# 06_FPGA_SOC_Part2.net
KiCad netlist of a schematic drawn in Altium Designer
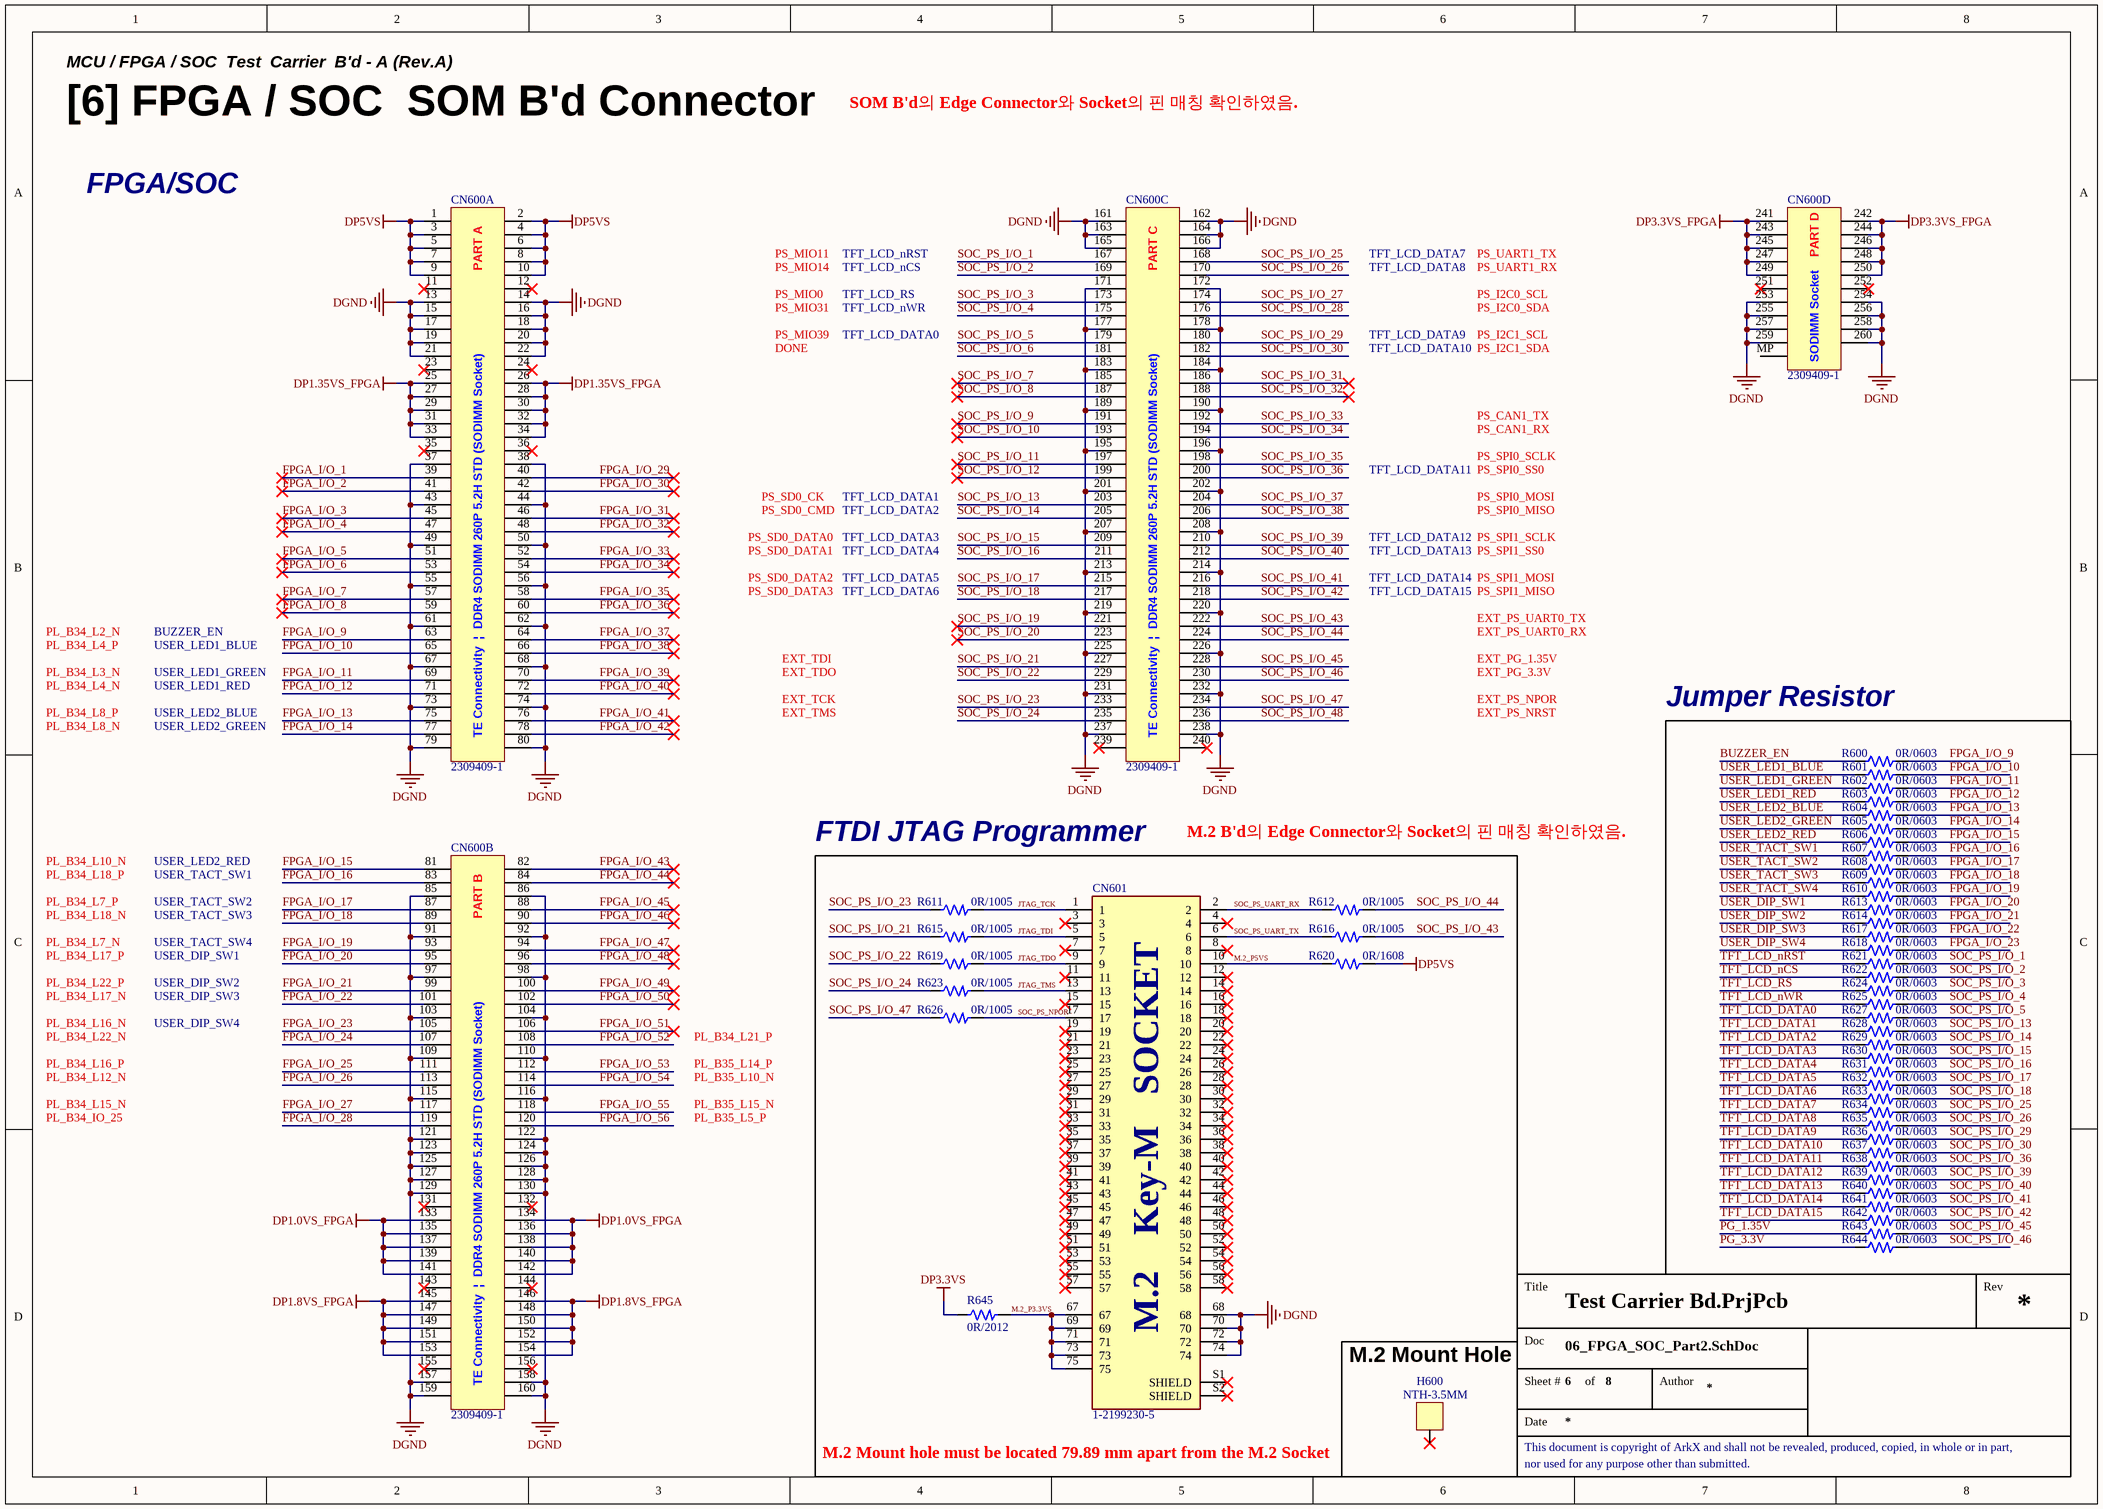
[diagram p0: 06_FPGA_SOC_Part2.SchDoc]

(export (version "E")
  (design (tool "Eeschema 10.0.6"))
  (components
    (comp (ref "CN600")
      (value "2309409-1")
      (footprint "CON_SODIMM_2309409-1")
      (fields (field (name "MANUFACTURER") "TE Connectivity") (field (name "LCSC PART #") "C5164025"))
      (libsource (lib "Arkx") (part "CON_SODIMM_2309409-1"))
    )
    (comp (ref "CN601")
      (value "1-2199230-5")
      (footprint "CON_M.2-KEY-M_FEMALE_1-2199230-5")
      (description "M.2 NGFF Key M Card Edge Connector 0.5mm Pitch 67 Position 4.2mm Height")
      (fields (field (name "MANUFACTURER") "TE Connectivity") (field (name "LCSC PART #") "C590854"))
      (libsource (lib "Arkx") (part "CON_M.2-KEY-M_FEMALE_1-2199230-5"))
    )
    (comp (ref "H600")
      (value "NTH-3.5MM")
      (footprint "HOLE_NTH-3.5MM")
      (description "Non-Through Hole 3.5mm")
      (libsource (lib "Arkx") (part "HOLE_NTH-3.5MM"))
    )
    (comp (ref "R600")
      (value "0R/0603")
      (footprint "RES 0603 (0201_inch)")
      (description "50mW Thick Film Resistors 25V ±1% 0Ω 0201  Chip Resistor - Surface Mount ROHS")
      (fields (field (name "LCSC PART #") "C106227"))
      (libsource (lib "Arkx") (part "RES_0R/0603/50mW"))
    )
    (comp (ref "R601")
      (value "0R/0603")
      (footprint "RES 0603 (0201_inch)")
      (description "50mW Thick Film Resistors 25V ±1% 0Ω 0201  Chip Resistor - Surface Mount ROHS")
      (fields (field (name "LCSC PART #") "C106227"))
      (libsource (lib "Arkx") (part "RES_0R/0603/50mW"))
    )
    (comp (ref "R602")
      (value "0R/0603")
      (footprint "RES 0603 (0201_inch)")
      (description "50mW Thick Film Resistors 25V ±1% 0Ω 0201  Chip Resistor - Surface Mount ROHS")
      (fields (field (name "LCSC PART #") "C106227"))
      (libsource (lib "Arkx") (part "RES_0R/0603/50mW"))
    )
    (comp (ref "R603")
      (value "0R/0603")
      (footprint "RES 0603 (0201_inch)")
      (description "50mW Thick Film Resistors 25V ±1% 0Ω 0201  Chip Resistor - Surface Mount ROHS")
      (fields (field (name "LCSC PART #") "C106227"))
      (libsource (lib "Arkx") (part "RES_0R/0603/50mW"))
    )
    (comp (ref "R604")
      (value "0R/0603")
      (footprint "RES 0603 (0201_inch)")
      (description "50mW Thick Film Resistors 25V ±1% 0Ω 0201  Chip Resistor - Surface Mount ROHS")
      (fields (field (name "LCSC PART #") "C106227"))
      (libsource (lib "Arkx") (part "RES_0R/0603/50mW"))
    )
    (comp (ref "R605")
      (value "0R/0603")
      (footprint "RES 0603 (0201_inch)")
      (description "50mW Thick Film Resistors 25V ±1% 0Ω 0201  Chip Resistor - Surface Mount ROHS")
      (fields (field (name "LCSC PART #") "C106227"))
      (libsource (lib "Arkx") (part "RES_0R/0603/50mW"))
    )
    (comp (ref "R606")
      (value "0R/0603")
      (footprint "RES 0603 (0201_inch)")
      (description "50mW Thick Film Resistors 25V ±1% 0Ω 0201  Chip Resistor - Surface Mount ROHS")
      (fields (field (name "LCSC PART #") "C106227"))
      (libsource (lib "Arkx") (part "RES_0R/0603/50mW"))
    )
    (comp (ref "R607")
      (value "0R/0603")
      (footprint "RES 0603 (0201_inch)")
      (description "50mW Thick Film Resistors 25V ±1% 0Ω 0201  Chip Resistor - Surface Mount ROHS")
      (fields (field (name "LCSC PART #") "C106227"))
      (libsource (lib "Arkx") (part "RES_0R/0603/50mW"))
    )
    (comp (ref "R608")
      (value "0R/0603")
      (footprint "RES 0603 (0201_inch)")
      (description "50mW Thick Film Resistors 25V ±1% 0Ω 0201  Chip Resistor - Surface Mount ROHS")
      (fields (field (name "LCSC PART #") "C106227"))
      (libsource (lib "Arkx") (part "RES_0R/0603/50mW"))
    )
    (comp (ref "R609")
      (value "0R/0603")
      (footprint "RES 0603 (0201_inch)")
      (description "50mW Thick Film Resistors 25V ±1% 0Ω 0201  Chip Resistor - Surface Mount ROHS")
      (fields (field (name "LCSC PART #") "C106227"))
      (libsource (lib "Arkx") (part "RES_0R/0603/50mW"))
    )
    (comp (ref "R610")
      (value "0R/0603")
      (footprint "RES 0603 (0201_inch)")
      (description "50mW Thick Film Resistors 25V ±1% 0Ω 0201  Chip Resistor - Surface Mount ROHS")
      (fields (field (name "LCSC PART #") "C106227"))
      (libsource (lib "Arkx") (part "RES_0R/0603/50mW"))
    )
    (comp (ref "R611")
      (value "0R/1005")
      (footprint "RES 1005 (0402_inch)")
      (description "RES_0R/1005/62.5mW")
      (fields (field (name "LCSC PART #") "C17168"))
      (libsource (lib "Arkx") (part "RES_0R/1005/62.5mW"))
    )
    (comp (ref "R612")
      (value "0R/1005")
      (footprint "RES 1005 (0402_inch)")
      (description "RES_0R/1005/62.5mW")
      (fields (field (name "LCSC PART #") "C17168"))
      (libsource (lib "Arkx") (part "RES_0R/1005/62.5mW"))
    )
    (comp (ref "R613")
      (value "0R/0603")
      (footprint "RES 0603 (0201_inch)")
      (description "50mW Thick Film Resistors 25V ±1% 0Ω 0201  Chip Resistor - Surface Mount ROHS")
      (fields (field (name "LCSC PART #") "C106227"))
      (libsource (lib "Arkx") (part "RES_0R/0603/50mW"))
    )
    (comp (ref "R614")
      (value "0R/0603")
      (footprint "RES 0603 (0201_inch)")
      (description "50mW Thick Film Resistors 25V ±1% 0Ω 0201  Chip Resistor - Surface Mount ROHS")
      (fields (field (name "LCSC PART #") "C106227"))
      (libsource (lib "Arkx") (part "RES_0R/0603/50mW"))
    )
    (comp (ref "R615")
      (value "0R/1005")
      (footprint "RES 1005 (0402_inch)")
      (description "RES_0R/1005/62.5mW")
      (fields (field (name "LCSC PART #") "C17168"))
      (libsource (lib "Arkx") (part "RES_0R/1005/62.5mW"))
    )
    (comp (ref "R616")
      (value "0R/1005")
      (footprint "RES 1005 (0402_inch)")
      (description "RES_0R/1005/62.5mW")
      (fields (field (name "LCSC PART #") "C17168"))
      (libsource (lib "Arkx") (part "RES_0R/1005/62.5mW"))
    )
    (comp (ref "R617")
      (value "0R/0603")
      (footprint "RES 0603 (0201_inch)")
      (description "50mW Thick Film Resistors 25V ±1% 0Ω 0201  Chip Resistor - Surface Mount ROHS")
      (fields (field (name "LCSC PART #") "C106227"))
      (libsource (lib "Arkx") (part "RES_0R/0603/50mW"))
    )
    (comp (ref "R618")
      (value "0R/0603")
      (footprint "RES 0603 (0201_inch)")
      (description "50mW Thick Film Resistors 25V ±1% 0Ω 0201  Chip Resistor - Surface Mount ROHS")
      (fields (field (name "LCSC PART #") "C106227"))
      (libsource (lib "Arkx") (part "RES_0R/0603/50mW"))
    )
    (comp (ref "R619")
      (value "0R/1005")
      (footprint "RES 1005 (0402_inch)")
      (description "RES_0R/1005/62.5mW")
      (fields (field (name "LCSC PART #") "C17168"))
      (libsource (lib "Arkx") (part "RES_0R/1005/62.5mW"))
    )
    (comp (ref "R620")
      (value "0R/1608")
      (footprint "RES 1608 (0603_inch)")
      (description "RES_0R/1608/0.1W")
      (fields (field (name "LCSC PART #") "C21189"))
      (libsource (lib "Arkx") (part "RES_0R/1608/0.1W"))
    )
    (comp (ref "R621")
      (value "0R/0603")
      (footprint "RES 0603 (0201_inch)")
      (description "50mW Thick Film Resistors 25V ±1% 0Ω 0201  Chip Resistor - Surface Mount ROHS")
      (fields (field (name "LCSC PART #") "C106227"))
      (libsource (lib "Arkx") (part "RES_0R/0603/50mW"))
    )
    (comp (ref "R622")
      (value "0R/0603")
      (footprint "RES 0603 (0201_inch)")
      (description "50mW Thick Film Resistors 25V ±1% 0Ω 0201  Chip Resistor - Surface Mount ROHS")
      (fields (field (name "LCSC PART #") "C106227"))
      (libsource (lib "Arkx") (part "RES_0R/0603/50mW"))
    )
    (comp (ref "R623")
      (value "0R/1005")
      (footprint "RES 1005 (0402_inch)")
      (description "RES_0R/1005/62.5mW")
      (fields (field (name "LCSC PART #") "C17168"))
      (libsource (lib "Arkx") (part "RES_0R/1005/62.5mW"))
    )
    (comp (ref "R624")
      (value "0R/0603")
      (footprint "RES 0603 (0201_inch)")
      (description "50mW Thick Film Resistors 25V ±1% 0Ω 0201  Chip Resistor - Surface Mount ROHS")
      (fields (field (name "LCSC PART #") "C106227"))
      (libsource (lib "Arkx") (part "RES_0R/0603/50mW"))
    )
    (comp (ref "R625")
      (value "0R/0603")
      (footprint "RES 0603 (0201_inch)")
      (description "50mW Thick Film Resistors 25V ±1% 0Ω 0201  Chip Resistor - Surface Mount ROHS")
      (fields (field (name "LCSC PART #") "C106227"))
      (libsource (lib "Arkx") (part "RES_0R/0603/50mW"))
    )
    (comp (ref "R626")
      (value "0R/1005")
      (footprint "RES 1005 (0402_inch)")
      (description "RES_0R/1005/62.5mW")
      (fields (field (name "LCSC PART #") "C17168"))
      (libsource (lib "Arkx") (part "RES_0R/1005/62.5mW"))
    )
    (comp (ref "R627")
      (value "0R/0603")
      (footprint "RES 0603 (0201_inch)")
      (description "50mW Thick Film Resistors 25V ±1% 0Ω 0201  Chip Resistor - Surface Mount ROHS")
      (fields (field (name "LCSC PART #") "C106227"))
      (libsource (lib "Arkx") (part "RES_0R/0603/50mW"))
    )
    (comp (ref "R628")
      (value "0R/0603")
      (footprint "RES 0603 (0201_inch)")
      (description "50mW Thick Film Resistors 25V ±1% 0Ω 0201  Chip Resistor - Surface Mount ROHS")
      (fields (field (name "LCSC PART #") "C106227"))
      (libsource (lib "Arkx") (part "RES_0R/0603/50mW"))
    )
    (comp (ref "R629")
      (value "0R/0603")
      (footprint "RES 0603 (0201_inch)")
      (description "50mW Thick Film Resistors 25V ±1% 0Ω 0201  Chip Resistor - Surface Mount ROHS")
      (fields (field (name "LCSC PART #") "C106227"))
      (libsource (lib "Arkx") (part "RES_0R/0603/50mW"))
    )
    (comp (ref "R630")
      (value "0R/0603")
      (footprint "RES 0603 (0201_inch)")
      (description "50mW Thick Film Resistors 25V ±1% 0Ω 0201  Chip Resistor - Surface Mount ROHS")
      (fields (field (name "LCSC PART #") "C106227"))
      (libsource (lib "Arkx") (part "RES_0R/0603/50mW"))
    )
    (comp (ref "R631")
      (value "0R/0603")
      (footprint "RES 0603 (0201_inch)")
      (description "50mW Thick Film Resistors 25V ±1% 0Ω 0201  Chip Resistor - Surface Mount ROHS")
      (fields (field (name "LCSC PART #") "C106227"))
      (libsource (lib "Arkx") (part "RES_0R/0603/50mW"))
    )
    (comp (ref "R632")
      (value "0R/0603")
      (footprint "RES 0603 (0201_inch)")
      (description "50mW Thick Film Resistors 25V ±1% 0Ω 0201  Chip Resistor - Surface Mount ROHS")
      (fields (field (name "LCSC PART #") "C106227"))
      (libsource (lib "Arkx") (part "RES_0R/0603/50mW"))
    )
    (comp (ref "R633")
      (value "0R/0603")
      (footprint "RES 0603 (0201_inch)")
      (description "50mW Thick Film Resistors 25V ±1% 0Ω 0201  Chip Resistor - Surface Mount ROHS")
      (fields (field (name "LCSC PART #") "C106227"))
      (libsource (lib "Arkx") (part "RES_0R/0603/50mW"))
    )
    (comp (ref "R634")
      (value "0R/0603")
      (footprint "RES 0603 (0201_inch)")
      (description "50mW Thick Film Resistors 25V ±1% 0Ω 0201  Chip Resistor - Surface Mount ROHS")
      (fields (field (name "LCSC PART #") "C106227"))
      (libsource (lib "Arkx") (part "RES_0R/0603/50mW"))
    )
    (comp (ref "R635")
      (value "0R/0603")
      (footprint "RES 0603 (0201_inch)")
      (description "50mW Thick Film Resistors 25V ±1% 0Ω 0201  Chip Resistor - Surface Mount ROHS")
      (fields (field (name "LCSC PART #") "C106227"))
      (libsource (lib "Arkx") (part "RES_0R/0603/50mW"))
    )
    (comp (ref "R636")
      (value "0R/0603")
      (footprint "RES 0603 (0201_inch)")
      (description "50mW Thick Film Resistors 25V ±1% 0Ω 0201  Chip Resistor - Surface Mount ROHS")
      (fields (field (name "LCSC PART #") "C106227"))
      (libsource (lib "Arkx") (part "RES_0R/0603/50mW"))
    )
    (comp (ref "R637")
      (value "0R/0603")
      (footprint "RES 0603 (0201_inch)")
      (description "50mW Thick Film Resistors 25V ±1% 0Ω 0201  Chip Resistor - Surface Mount ROHS")
      (fields (field (name "LCSC PART #") "C106227"))
      (libsource (lib "Arkx") (part "RES_0R/0603/50mW"))
    )
    (comp (ref "R638")
      (value "0R/0603")
      (footprint "RES 0603 (0201_inch)")
      (description "50mW Thick Film Resistors 25V ±1% 0Ω 0201  Chip Resistor - Surface Mount ROHS")
      (fields (field (name "LCSC PART #") "C106227"))
      (libsource (lib "Arkx") (part "RES_0R/0603/50mW"))
    )
    (comp (ref "R639")
      (value "0R/0603")
      (footprint "RES 0603 (0201_inch)")
      (description "50mW Thick Film Resistors 25V ±1% 0Ω 0201  Chip Resistor - Surface Mount ROHS")
      (fields (field (name "LCSC PART #") "C106227"))
      (libsource (lib "Arkx") (part "RES_0R/0603/50mW"))
    )
    (comp (ref "R640")
      (value "0R/0603")
      (footprint "RES 0603 (0201_inch)")
      (description "50mW Thick Film Resistors 25V ±1% 0Ω 0201  Chip Resistor - Surface Mount ROHS")
      (fields (field (name "LCSC PART #") "C106227"))
      (libsource (lib "Arkx") (part "RES_0R/0603/50mW"))
    )
    (comp (ref "R641")
      (value "0R/0603")
      (footprint "RES 0603 (0201_inch)")
      (description "50mW Thick Film Resistors 25V ±1% 0Ω 0201  Chip Resistor - Surface Mount ROHS")
      (fields (field (name "LCSC PART #") "C106227"))
      (libsource (lib "Arkx") (part "RES_0R/0603/50mW"))
    )
    (comp (ref "R642")
      (value "0R/0603")
      (footprint "RES 0603 (0201_inch)")
      (description "50mW Thick Film Resistors 25V ±1% 0Ω 0201  Chip Resistor - Surface Mount ROHS")
      (fields (field (name "LCSC PART #") "C106227"))
      (libsource (lib "Arkx") (part "RES_0R/0603/50mW"))
    )
    (comp (ref "R643")
      (value "0R/0603")
      (footprint "RES 0603 (0201_inch)")
      (description "50mW Thick Film Resistors 25V ±1% 0Ω 0201  Chip Resistor - Surface Mount ROHS")
      (fields (field (name "LCSC PART #") "C106227"))
      (libsource (lib "Arkx") (part "RES_0R/0603/50mW"))
    )
    (comp (ref "R644")
      (value "0R/0603")
      (footprint "RES 0603 (0201_inch)")
      (description "50mW Thick Film Resistors 25V ±1% 0Ω 0201  Chip Resistor - Surface Mount ROHS")
      (fields (field (name "LCSC PART #") "C106227"))
      (libsource (lib "Arkx") (part "RES_0R/0603/50mW"))
    )
    (comp (ref "R645")
      (value "0R/2012")
      (footprint "RES 2012 (0805_inch)")
      (description "RES_0R/2012/0.125W")
      (fields (field (name "LCSC PART #") "C17477"))
      (libsource (lib "Arkx") (part "RES_0R/2012/0.125W"))
    )
  )
  (nets
    (net (code "1") (name "/BUZZER_EN") (class "Default")
      (node (ref "R600") (pin "1") (pinfunction "1_1") (pintype "passive"))
    )
    (net (code "2") (name "/FPGA_I{slash}O_1") (class "Default")
      (node (ref "CN600") (pin "39") (pinfunction "39_39") (pintype "passive+no_connect"))
    )
    (net (code "3") (name "/FPGA_I{slash}O_2") (class "Default")
      (node (ref "CN600") (pin "41") (pinfunction "41_41") (pintype "passive+no_connect"))
    )
    (net (code "4") (name "/FPGA_I{slash}O_3") (class "Default")
      (node (ref "CN600") (pin "45") (pinfunction "45_45") (pintype "passive+no_connect"))
    )
    (net (code "5") (name "/FPGA_I{slash}O_4") (class "Default")
      (node (ref "CN600") (pin "47") (pinfunction "47_47") (pintype "passive+no_connect"))
    )
    (net (code "6") (name "/FPGA_I{slash}O_5") (class "Default")
      (node (ref "CN600") (pin "51") (pinfunction "51_51") (pintype "passive+no_connect"))
    )
    (net (code "7") (name "/FPGA_I{slash}O_6") (class "Default")
      (node (ref "CN600") (pin "53") (pinfunction "53_53") (pintype "passive+no_connect"))
    )
    (net (code "8") (name "/FPGA_I{slash}O_7") (class "Default")
      (node (ref "CN600") (pin "57") (pinfunction "57_57") (pintype "passive+no_connect"))
    )
    (net (code "9") (name "/FPGA_I{slash}O_8") (class "Default")
      (node (ref "CN600") (pin "59") (pinfunction "59_59") (pintype "passive+no_connect"))
    )
    (net (code "10") (name "/FPGA_I{slash}O_9") (class "Default")
      (node (ref "CN600") (pin "63") (pinfunction "63_63") (pintype "passive"))
      (node (ref "R600") (pin "2") (pinfunction "2_2") (pintype "passive"))
    )
    (net (code "11") (name "/FPGA_I{slash}O_10") (class "Default")
      (node (ref "CN600") (pin "65") (pinfunction "65_65") (pintype "passive"))
      (node (ref "R601") (pin "2") (pinfunction "2_2") (pintype "passive"))
    )
    (net (code "12") (name "/FPGA_I{slash}O_11") (class "Default")
      (node (ref "CN600") (pin "69") (pinfunction "69_69") (pintype "passive"))
      (node (ref "R602") (pin "2") (pinfunction "2_2") (pintype "passive"))
    )
    (net (code "13") (name "/FPGA_I{slash}O_12") (class "Default")
      (node (ref "CN600") (pin "71") (pinfunction "71_71") (pintype "passive"))
      (node (ref "R603") (pin "2") (pinfunction "2_2") (pintype "passive"))
    )
    (net (code "14") (name "/FPGA_I{slash}O_13") (class "Default")
      (node (ref "CN600") (pin "75") (pinfunction "75_75") (pintype "passive"))
      (node (ref "R604") (pin "2") (pinfunction "2_2") (pintype "passive"))
    )
    (net (code "15") (name "/FPGA_I{slash}O_14") (class "Default")
      (node (ref "CN600") (pin "77") (pinfunction "77_77") (pintype "passive"))
      (node (ref "R605") (pin "2") (pinfunction "2_2") (pintype "passive"))
    )
    (net (code "16") (name "/FPGA_I{slash}O_15") (class "Default")
      (node (ref "CN600") (pin "81") (pinfunction "81_81") (pintype "passive"))
      (node (ref "R606") (pin "2") (pinfunction "2_2") (pintype "passive"))
    )
    (net (code "17") (name "/FPGA_I{slash}O_16") (class "Default")
      (node (ref "CN600") (pin "83") (pinfunction "83_83") (pintype "passive"))
      (node (ref "R607") (pin "2") (pinfunction "2_2") (pintype "passive"))
    )
    (net (code "18") (name "/FPGA_I{slash}O_17") (class "Default")
      (node (ref "CN600") (pin "87") (pinfunction "87_87") (pintype "passive"))
      (node (ref "R608") (pin "2") (pinfunction "2_2") (pintype "passive"))
    )
    (net (code "19") (name "/FPGA_I{slash}O_18") (class "Default")
      (node (ref "CN600") (pin "89") (pinfunction "89_89") (pintype "passive"))
      (node (ref "R609") (pin "2") (pinfunction "2_2") (pintype "passive"))
    )
    (net (code "20") (name "/FPGA_I{slash}O_19") (class "Default")
      (node (ref "CN600") (pin "93") (pinfunction "93_93") (pintype "passive"))
      (node (ref "R610") (pin "2") (pinfunction "2_2") (pintype "passive"))
    )
    (net (code "21") (name "/FPGA_I{slash}O_20") (class "Default")
      (node (ref "CN600") (pin "95") (pinfunction "95_95") (pintype "passive"))
      (node (ref "R613") (pin "2") (pinfunction "2_2") (pintype "passive"))
    )
    (net (code "22") (name "/FPGA_I{slash}O_21") (class "Default")
      (node (ref "CN600") (pin "99") (pinfunction "99_99") (pintype "passive"))
      (node (ref "R614") (pin "2") (pinfunction "2_2") (pintype "passive"))
    )
    (net (code "23") (name "/FPGA_I{slash}O_22") (class "Default")
      (node (ref "CN600") (pin "101") (pinfunction "101_101") (pintype "passive"))
      (node (ref "R617") (pin "2") (pinfunction "2_2") (pintype "passive"))
    )
    (net (code "24") (name "/FPGA_I{slash}O_23") (class "Default")
      (node (ref "CN600") (pin "105") (pinfunction "105_105") (pintype "passive"))
      (node (ref "R618") (pin "2") (pinfunction "2_2") (pintype "passive"))
    )
    (net (code "25") (name "/FPGA_I{slash}O_24") (class "Default")
      (node (ref "CN600") (pin "107") (pinfunction "107_107") (pintype "passive"))
    )
    (net (code "26") (name "/FPGA_I{slash}O_25") (class "Default")
      (node (ref "CN600") (pin "111") (pinfunction "111_111") (pintype "passive"))
    )
    (net (code "27") (name "/FPGA_I{slash}O_26") (class "Default")
      (node (ref "CN600") (pin "113") (pinfunction "113_113") (pintype "passive"))
    )
    (net (code "28") (name "/FPGA_I{slash}O_27") (class "Default")
      (node (ref "CN600") (pin "117") (pinfunction "117_117") (pintype "passive"))
    )
    (net (code "29") (name "/FPGA_I{slash}O_28") (class "Default")
      (node (ref "CN600") (pin "119") (pinfunction "119_119") (pintype "passive"))
    )
    (net (code "30") (name "/FPGA_I{slash}O_29") (class "Default")
      (node (ref "CN600") (pin "40") (pinfunction "40_40") (pintype "passive+no_connect"))
    )
    (net (code "31") (name "/FPGA_I{slash}O_30") (class "Default")
      (node (ref "CN600") (pin "42") (pinfunction "42_42") (pintype "passive+no_connect"))
    )
    (net (code "32") (name "/FPGA_I{slash}O_31") (class "Default")
      (node (ref "CN600") (pin "46") (pinfunction "46_46") (pintype "passive+no_connect"))
    )
    (net (code "33") (name "/FPGA_I{slash}O_32") (class "Default")
      (node (ref "CN600") (pin "48") (pinfunction "48_48") (pintype "passive+no_connect"))
    )
    (net (code "34") (name "/FPGA_I{slash}O_33") (class "Default")
      (node (ref "CN600") (pin "52") (pinfunction "52_52") (pintype "passive+no_connect"))
    )
    (net (code "35") (name "/FPGA_I{slash}O_34") (class "Default")
      (node (ref "CN600") (pin "54") (pinfunction "54_54") (pintype "passive+no_connect"))
    )
    (net (code "36") (name "/FPGA_I{slash}O_35") (class "Default")
      (node (ref "CN600") (pin "58") (pinfunction "58_58") (pintype "passive+no_connect"))
    )
    (net (code "37") (name "/FPGA_I{slash}O_36") (class "Default")
      (node (ref "CN600") (pin "60") (pinfunction "60_60") (pintype "passive+no_connect"))
    )
    (net (code "38") (name "/FPGA_I{slash}O_37") (class "Default")
      (node (ref "CN600") (pin "64") (pinfunction "64_64") (pintype "passive+no_connect"))
    )
    (net (code "39") (name "/FPGA_I{slash}O_38") (class "Default")
      (node (ref "CN600") (pin "66") (pinfunction "66_66") (pintype "passive+no_connect"))
    )
    (net (code "40") (name "/FPGA_I{slash}O_39") (class "Default")
      (node (ref "CN600") (pin "70") (pinfunction "70_70") (pintype "passive+no_connect"))
    )
    (net (code "41") (name "/FPGA_I{slash}O_40") (class "Default")
      (node (ref "CN600") (pin "72") (pinfunction "72_72") (pintype "passive+no_connect"))
    )
    (net (code "42") (name "/FPGA_I{slash}O_41") (class "Default")
      (node (ref "CN600") (pin "76") (pinfunction "76_76") (pintype "passive+no_connect"))
    )
    (net (code "43") (name "/FPGA_I{slash}O_42") (class "Default")
      (node (ref "CN600") (pin "78") (pinfunction "78_78") (pintype "passive+no_connect"))
    )
    (net (code "44") (name "/FPGA_I{slash}O_43") (class "Default")
      (node (ref "CN600") (pin "82") (pinfunction "82_82") (pintype "passive+no_connect"))
    )
    (net (code "45") (name "/FPGA_I{slash}O_44") (class "Default")
      (node (ref "CN600") (pin "84") (pinfunction "84_84") (pintype "passive+no_connect"))
    )
    (net (code "46") (name "/FPGA_I{slash}O_45") (class "Default")
      (node (ref "CN600") (pin "88") (pinfunction "88_88") (pintype "passive+no_connect"))
    )
    (net (code "47") (name "/FPGA_I{slash}O_46") (class "Default")
      (node (ref "CN600") (pin "90") (pinfunction "90_90") (pintype "passive+no_connect"))
    )
    (net (code "48") (name "/FPGA_I{slash}O_47") (class "Default")
      (node (ref "CN600") (pin "94") (pinfunction "94_94") (pintype "passive+no_connect"))
    )
    (net (code "49") (name "/FPGA_I{slash}O_48") (class "Default")
      (node (ref "CN600") (pin "96") (pinfunction "96_96") (pintype "passive+no_connect"))
    )
    (net (code "50") (name "/FPGA_I{slash}O_49") (class "Default")
      (node (ref "CN600") (pin "100") (pinfunction "100_100") (pintype "passive+no_connect"))
    )
    (net (code "51") (name "/FPGA_I{slash}O_50") (class "Default")
      (node (ref "CN600") (pin "102") (pinfunction "102_102") (pintype "passive+no_connect"))
    )
    (net (code "52") (name "/FPGA_I{slash}O_51") (class "Default")
      (node (ref "CN600") (pin "106") (pinfunction "106_106") (pintype "passive+no_connect"))
    )
    (net (code "53") (name "/FPGA_I{slash}O_52") (class "Default")
      (node (ref "CN600") (pin "108") (pinfunction "108_108") (pintype "passive"))
    )
    (net (code "54") (name "/FPGA_I{slash}O_53") (class "Default")
      (node (ref "CN600") (pin "112") (pinfunction "112_112") (pintype "passive"))
    )
    (net (code "55") (name "/FPGA_I{slash}O_54") (class "Default")
      (node (ref "CN600") (pin "114") (pinfunction "114_114") (pintype "passive"))
    )
    (net (code "56") (name "/FPGA_I{slash}O_55") (class "Default")
      (node (ref "CN600") (pin "118") (pinfunction "118_118") (pintype "passive"))
    )
    (net (code "57") (name "/FPGA_I{slash}O_56") (class "Default")
      (node (ref "CN600") (pin "120") (pinfunction "120_120") (pintype "passive"))
    )
    (net (code "58") (name "/JTAG_TCK") (class "Default")
      (node (ref "CN601") (pin "1") (pinfunction "1_1") (pintype "passive"))
      (node (ref "R611") (pin "2") (pinfunction "2_2") (pintype "passive"))
    )
    (net (code "59") (name "/JTAG_TDI") (class "Default")
      (node (ref "CN601") (pin "5") (pinfunction "5_5") (pintype "passive"))
      (node (ref "R615") (pin "2") (pinfunction "2_2") (pintype "passive"))
    )
    (net (code "60") (name "/JTAG_TDO") (class "Default")
      (node (ref "CN601") (pin "9") (pinfunction "9_9") (pintype "passive"))
      (node (ref "R619") (pin "2") (pinfunction "2_2") (pintype "passive"))
    )
    (net (code "61") (name "/JTAG_TMS") (class "Default")
      (node (ref "CN601") (pin "13") (pinfunction "13_13") (pintype "passive"))
      (node (ref "R623") (pin "2") (pinfunction "2_2") (pintype "passive"))
    )
    (net (code "62") (name "/M.2_P3.3VS") (class "Default")
      (node (ref "CN601") (pin "67") (pinfunction "67_67") (pintype "passive"))
      (node (ref "CN601") (pin "69") (pinfunction "69_69") (pintype "passive"))
      (node (ref "CN601") (pin "71") (pinfunction "71_71") (pintype "passive"))
      (node (ref "CN601") (pin "73") (pinfunction "73_73") (pintype "passive"))
      (node (ref "CN601") (pin "75") (pinfunction "75_75") (pintype "passive"))
      (node (ref "R645") (pin "2") (pinfunction "2_2") (pintype "passive"))
    )
    (net (code "63") (name "/M.2_P5VS") (class "Default")
      (node (ref "CN601") (pin "10") (pinfunction "10_10") (pintype "passive"))
      (node (ref "R620") (pin "1") (pinfunction "1_1") (pintype "passive"))
    )
    (net (code "64") (name "/PG_1.35V") (class "Default")
      (node (ref "R643") (pin "1") (pinfunction "1_1") (pintype "passive"))
    )
    (net (code "65") (name "/PG_3.3V") (class "Default")
      (node (ref "R644") (pin "1") (pinfunction "1_1") (pintype "passive"))
    )
    (net (code "66") (name "/SOC_PS_I{slash}O_1") (class "Default")
      (node (ref "CN600") (pin "167") (pinfunction "167_167") (pintype "passive"))
      (node (ref "R621") (pin "2") (pinfunction "2_2") (pintype "passive"))
    )
    (net (code "67") (name "/SOC_PS_I{slash}O_2") (class "Default")
      (node (ref "CN600") (pin "169") (pinfunction "169_169") (pintype "passive"))
      (node (ref "R622") (pin "2") (pinfunction "2_2") (pintype "passive"))
    )
    (net (code "68") (name "/SOC_PS_I{slash}O_3") (class "Default")
      (node (ref "CN600") (pin "173") (pinfunction "173_173") (pintype "passive"))
      (node (ref "R624") (pin "2") (pinfunction "2_2") (pintype "passive"))
    )
    (net (code "69") (name "/SOC_PS_I{slash}O_4") (class "Default")
      (node (ref "CN600") (pin "175") (pinfunction "175_175") (pintype "passive"))
      (node (ref "R625") (pin "2") (pinfunction "2_2") (pintype "passive"))
    )
    (net (code "70") (name "/SOC_PS_I{slash}O_5") (class "Default")
      (node (ref "CN600") (pin "179") (pinfunction "179_179") (pintype "passive"))
      (node (ref "R627") (pin "2") (pinfunction "2_2") (pintype "passive"))
    )
    (net (code "71") (name "/SOC_PS_I{slash}O_6") (class "Default")
      (node (ref "CN600") (pin "181") (pinfunction "181_181") (pintype "passive"))
    )
    (net (code "72") (name "/SOC_PS_I{slash}O_7") (class "Default")
      (node (ref "CN600") (pin "185") (pinfunction "185_185") (pintype "passive+no_connect"))
    )
    (net (code "73") (name "/SOC_PS_I{slash}O_8") (class "Default")
      (node (ref "CN600") (pin "187") (pinfunction "187_187") (pintype "passive+no_connect"))
    )
    (net (code "74") (name "/SOC_PS_I{slash}O_9") (class "Default")
      (node (ref "CN600") (pin "191") (pinfunction "191_191") (pintype "passive+no_connect"))
    )
    (net (code "75") (name "/SOC_PS_I{slash}O_10") (class "Default")
      (node (ref "CN600") (pin "193") (pinfunction "193_193") (pintype "passive+no_connect"))
    )
    (net (code "76") (name "/SOC_PS_I{slash}O_11") (class "Default")
      (node (ref "CN600") (pin "197") (pinfunction "197_197") (pintype "passive+no_connect"))
    )
    (net (code "77") (name "/SOC_PS_I{slash}O_12") (class "Default")
      (node (ref "CN600") (pin "199") (pinfunction "199_199") (pintype "passive+no_connect"))
    )
    (net (code "78") (name "/SOC_PS_I{slash}O_13") (class "Default")
      (node (ref "CN600") (pin "203") (pinfunction "203_203") (pintype "passive"))
      (node (ref "R628") (pin "2") (pinfunction "2_2") (pintype "passive"))
    )
    (net (code "79") (name "/SOC_PS_I{slash}O_14") (class "Default")
      (node (ref "CN600") (pin "205") (pinfunction "205_205") (pintype "passive"))
      (node (ref "R629") (pin "2") (pinfunction "2_2") (pintype "passive"))
    )
    (net (code "80") (name "/SOC_PS_I{slash}O_15") (class "Default")
      (node (ref "CN600") (pin "209") (pinfunction "209_209") (pintype "passive"))
      (node (ref "R630") (pin "2") (pinfunction "2_2") (pintype "passive"))
    )
    (net (code "81") (name "/SOC_PS_I{slash}O_16") (class "Default")
      (node (ref "CN600") (pin "211") (pinfunction "211_211") (pintype "passive"))
      (node (ref "R631") (pin "2") (pinfunction "2_2") (pintype "passive"))
    )
    (net (code "82") (name "/SOC_PS_I{slash}O_17") (class "Default")
      (node (ref "CN600") (pin "215") (pinfunction "215_215") (pintype "passive"))
      (node (ref "R632") (pin "2") (pinfunction "2_2") (pintype "passive"))
    )
    (net (code "83") (name "/SOC_PS_I{slash}O_18") (class "Default")
      (node (ref "CN600") (pin "217") (pinfunction "217_217") (pintype "passive"))
      (node (ref "R633") (pin "2") (pinfunction "2_2") (pintype "passive"))
    )
    (net (code "84") (name "/SOC_PS_I{slash}O_19") (class "Default")
      (node (ref "CN600") (pin "221") (pinfunction "221_221") (pintype "passive+no_connect"))
    )
    (net (code "85") (name "/SOC_PS_I{slash}O_20") (class "Default")
      (node (ref "CN600") (pin "223") (pinfunction "223_223") (pintype "passive+no_connect"))
    )
    (net (code "86") (name "/SOC_PS_I{slash}O_21") (class "Default")
      (node (ref "CN600") (pin "227") (pinfunction "227_227") (pintype "passive"))
      (node (ref "R615") (pin "1") (pinfunction "1_1") (pintype "passive"))
    )
    (net (code "87") (name "/SOC_PS_I{slash}O_22") (class "Default")
      (node (ref "CN600") (pin "229") (pinfunction "229_229") (pintype "passive"))
      (node (ref "R619") (pin "1") (pinfunction "1_1") (pintype "passive"))
    )
    (net (code "88") (name "/SOC_PS_I{slash}O_23") (class "Default")
      (node (ref "CN600") (pin "233") (pinfunction "233_233") (pintype "passive"))
      (node (ref "R611") (pin "1") (pinfunction "1_1") (pintype "passive"))
    )
    (net (code "89") (name "/SOC_PS_I{slash}O_24") (class "Default")
      (node (ref "CN600") (pin "235") (pinfunction "235_235") (pintype "passive"))
      (node (ref "R623") (pin "1") (pinfunction "1_1") (pintype "passive"))
    )
    (net (code "90") (name "/SOC_PS_I{slash}O_25") (class "Default")
      (node (ref "CN600") (pin "168") (pinfunction "168_168") (pintype "passive"))
      (node (ref "R634") (pin "2") (pinfunction "2_2") (pintype "passive"))
    )
    (net (code "91") (name "/SOC_PS_I{slash}O_26") (class "Default")
      (node (ref "CN600") (pin "170") (pinfunction "170_170") (pintype "passive"))
      (node (ref "R635") (pin "2") (pinfunction "2_2") (pintype "passive"))
    )
    (net (code "92") (name "/SOC_PS_I{slash}O_27") (class "Default")
      (node (ref "CN600") (pin "174") (pinfunction "174_174") (pintype "passive"))
    )
    (net (code "93") (name "/SOC_PS_I{slash}O_28") (class "Default")
      (node (ref "CN600") (pin "176") (pinfunction "176_176") (pintype "passive"))
    )
    (net (code "94") (name "/SOC_PS_I{slash}O_29") (class "Default")
      (node (ref "CN600") (pin "180") (pinfunction "180_180") (pintype "passive"))
      (node (ref "R636") (pin "2") (pinfunction "2_2") (pintype "passive"))
    )
    (net (code "95") (name "/SOC_PS_I{slash}O_30") (class "Default")
      (node (ref "CN600") (pin "182") (pinfunction "182_182") (pintype "passive"))
      (node (ref "R637") (pin "2") (pinfunction "2_2") (pintype "passive"))
    )
    (net (code "96") (name "/SOC_PS_I{slash}O_31") (class "Default")
      (node (ref "CN600") (pin "186") (pinfunction "186_186") (pintype "passive+no_connect"))
    )
    (net (code "97") (name "/SOC_PS_I{slash}O_32") (class "Default")
      (node (ref "CN600") (pin "188") (pinfunction "188_188") (pintype "passive+no_connect"))
    )
    (net (code "98") (name "/SOC_PS_I{slash}O_33") (class "Default")
      (node (ref "CN600") (pin "192") (pinfunction "192_192") (pintype "passive"))
    )
    (net (code "99") (name "/SOC_PS_I{slash}O_34") (class "Default")
      (node (ref "CN600") (pin "194") (pinfunction "194_194") (pintype "passive"))
    )
    (net (code "100") (name "/SOC_PS_I{slash}O_35") (class "Default")
      (node (ref "CN600") (pin "198") (pinfunction "198_198") (pintype "passive"))
    )
    (net (code "101") (name "/SOC_PS_I{slash}O_36") (class "Default")
      (node (ref "CN600") (pin "200") (pinfunction "200_200") (pintype "passive"))
      (node (ref "R638") (pin "2") (pinfunction "2_2") (pintype "passive"))
    )
    (net (code "102") (name "/SOC_PS_I{slash}O_37") (class "Default")
      (node (ref "CN600") (pin "204") (pinfunction "204_204") (pintype "passive"))
    )
    (net (code "103") (name "/SOC_PS_I{slash}O_38") (class "Default")
      (node (ref "CN600") (pin "206") (pinfunction "206_206") (pintype "passive"))
    )
    (net (code "104") (name "/SOC_PS_I{slash}O_39") (class "Default")
      (node (ref "CN600") (pin "210") (pinfunction "210_210") (pintype "passive"))
      (node (ref "R639") (pin "2") (pinfunction "2_2") (pintype "passive"))
    )
    (net (code "105") (name "/SOC_PS_I{slash}O_40") (class "Default")
      (node (ref "CN600") (pin "212") (pinfunction "212_212") (pintype "passive"))
      (node (ref "R640") (pin "2") (pinfunction "2_2") (pintype "passive"))
    )
    (net (code "106") (name "/SOC_PS_I{slash}O_41") (class "Default")
      (node (ref "CN600") (pin "216") (pinfunction "216_216") (pintype "passive"))
      (node (ref "R641") (pin "2") (pinfunction "2_2") (pintype "passive"))
    )
    (net (code "107") (name "/SOC_PS_I{slash}O_42") (class "Default")
      (node (ref "CN600") (pin "218") (pinfunction "218_218") (pintype "passive"))
      (node (ref "R642") (pin "2") (pinfunction "2_2") (pintype "passive"))
    )
    (net (code "108") (name "/SOC_PS_I{slash}O_43") (class "Default")
      (node (ref "CN600") (pin "222") (pinfunction "222_222") (pintype "passive"))
      (node (ref "R616") (pin "2") (pinfunction "2_2") (pintype "passive"))
    )
    (net (code "109") (name "/SOC_PS_I{slash}O_44") (class "Default")
      (node (ref "CN600") (pin "224") (pinfunction "224_224") (pintype "passive"))
      (node (ref "R612") (pin "2") (pinfunction "2_2") (pintype "passive"))
    )
    (net (code "110") (name "/SOC_PS_I{slash}O_45") (class "Default")
      (node (ref "CN600") (pin "228") (pinfunction "228_228") (pintype "passive"))
      (node (ref "R643") (pin "2") (pinfunction "2_2") (pintype "passive"))
    )
    (net (code "111") (name "/SOC_PS_I{slash}O_46") (class "Default")
      (node (ref "CN600") (pin "230") (pinfunction "230_230") (pintype "passive"))
      (node (ref "R644") (pin "2") (pinfunction "2_2") (pintype "passive"))
    )
    (net (code "112") (name "/SOC_PS_I{slash}O_47") (class "Default")
      (node (ref "CN600") (pin "234") (pinfunction "234_234") (pintype "passive"))
      (node (ref "R626") (pin "1") (pinfunction "1_1") (pintype "passive"))
    )
    (net (code "113") (name "/SOC_PS_I{slash}O_48") (class "Default")
      (node (ref "CN600") (pin "236") (pinfunction "236_236") (pintype "passive"))
    )
    (net (code "114") (name "/SOC_PS_NPOR") (class "Default")
      (node (ref "CN601") (pin "17") (pinfunction "17_17") (pintype "passive"))
      (node (ref "R626") (pin "2") (pinfunction "2_2") (pintype "passive"))
    )
    (net (code "115") (name "/SOC_PS_UART_RX") (class "Default")
      (node (ref "CN601") (pin "2") (pinfunction "2_2") (pintype "passive"))
      (node (ref "R612") (pin "1") (pinfunction "1_1") (pintype "passive"))
    )
    (net (code "116") (name "/SOC_PS_UART_TX") (class "Default")
      (node (ref "CN601") (pin "6") (pinfunction "6_6") (pintype "passive"))
      (node (ref "R616") (pin "1") (pinfunction "1_1") (pintype "passive"))
    )
    (net (code "117") (name "/TFT_LCD_DATA0") (class "Default")
      (node (ref "R627") (pin "1") (pinfunction "1_1") (pintype "passive"))
    )
    (net (code "118") (name "/TFT_LCD_DATA1") (class "Default")
      (node (ref "R628") (pin "1") (pinfunction "1_1") (pintype "passive"))
    )
    (net (code "119") (name "/TFT_LCD_DATA2") (class "Default")
      (node (ref "R629") (pin "1") (pinfunction "1_1") (pintype "passive"))
    )
    (net (code "120") (name "/TFT_LCD_DATA3") (class "Default")
      (node (ref "R630") (pin "1") (pinfunction "1_1") (pintype "passive"))
    )
    (net (code "121") (name "/TFT_LCD_DATA4") (class "Default")
      (node (ref "R631") (pin "1") (pinfunction "1_1") (pintype "passive"))
    )
    (net (code "122") (name "/TFT_LCD_DATA5") (class "Default")
      (node (ref "R632") (pin "1") (pinfunction "1_1") (pintype "passive"))
    )
    (net (code "123") (name "/TFT_LCD_DATA6") (class "Default")
      (node (ref "R633") (pin "1") (pinfunction "1_1") (pintype "passive"))
    )
    (net (code "124") (name "/TFT_LCD_DATA7") (class "Default")
      (node (ref "R634") (pin "1") (pinfunction "1_1") (pintype "passive"))
    )
    (net (code "125") (name "/TFT_LCD_DATA8") (class "Default")
      (node (ref "R635") (pin "1") (pinfunction "1_1") (pintype "passive"))
    )
    (net (code "126") (name "/TFT_LCD_DATA9") (class "Default")
      (node (ref "R636") (pin "1") (pinfunction "1_1") (pintype "passive"))
    )
    (net (code "127") (name "/TFT_LCD_DATA10") (class "Default")
      (node (ref "R637") (pin "1") (pinfunction "1_1") (pintype "passive"))
    )
    (net (code "128") (name "/TFT_LCD_DATA11") (class "Default")
      (node (ref "R638") (pin "1") (pinfunction "1_1") (pintype "passive"))
    )
    (net (code "129") (name "/TFT_LCD_DATA12") (class "Default")
      (node (ref "R639") (pin "1") (pinfunction "1_1") (pintype "passive"))
    )
    (net (code "130") (name "/TFT_LCD_DATA13") (class "Default")
      (node (ref "R640") (pin "1") (pinfunction "1_1") (pintype "passive"))
    )
    (net (code "131") (name "/TFT_LCD_DATA14") (class "Default")
      (node (ref "R641") (pin "1") (pinfunction "1_1") (pintype "passive"))
    )
    (net (code "132") (name "/TFT_LCD_DATA15") (class "Default")
      (node (ref "R642") (pin "1") (pinfunction "1_1") (pintype "passive"))
    )
    (net (code "133") (name "/TFT_LCD_RS") (class "Default")
      (node (ref "R624") (pin "1") (pinfunction "1_1") (pintype "passive"))
    )
    (net (code "134") (name "/TFT_LCD_nCS") (class "Default")
      (node (ref "R622") (pin "1") (pinfunction "1_1") (pintype "passive"))
    )
    (net (code "135") (name "/TFT_LCD_nRST") (class "Default")
      (node (ref "R621") (pin "1") (pinfunction "1_1") (pintype "passive"))
    )
    (net (code "136") (name "/TFT_LCD_nWR") (class "Default")
      (node (ref "R625") (pin "1") (pinfunction "1_1") (pintype "passive"))
    )
    (net (code "137") (name "/USER_DIP_SW1") (class "Default")
      (node (ref "R613") (pin "1") (pinfunction "1_1") (pintype "passive"))
    )
    (net (code "138") (name "/USER_DIP_SW2") (class "Default")
      (node (ref "R614") (pin "1") (pinfunction "1_1") (pintype "passive"))
    )
    (net (code "139") (name "/USER_DIP_SW3") (class "Default")
      (node (ref "R617") (pin "1") (pinfunction "1_1") (pintype "passive"))
    )
    (net (code "140") (name "/USER_DIP_SW4") (class "Default")
      (node (ref "R618") (pin "1") (pinfunction "1_1") (pintype "passive"))
    )
    (net (code "141") (name "/USER_LED1_BLUE") (class "Default")
      (node (ref "R601") (pin "1") (pinfunction "1_1") (pintype "passive"))
    )
    (net (code "142") (name "/USER_LED1_GREEN") (class "Default")
      (node (ref "R602") (pin "1") (pinfunction "1_1") (pintype "passive"))
    )
    (net (code "143") (name "/USER_LED1_RED") (class "Default")
      (node (ref "R603") (pin "1") (pinfunction "1_1") (pintype "passive"))
    )
    (net (code "144") (name "/USER_LED2_BLUE") (class "Default")
      (node (ref "R604") (pin "1") (pinfunction "1_1") (pintype "passive"))
    )
    (net (code "145") (name "/USER_LED2_GREEN") (class "Default")
      (node (ref "R605") (pin "1") (pinfunction "1_1") (pintype "passive"))
    )
    (net (code "146") (name "/USER_LED2_RED") (class "Default")
      (node (ref "R606") (pin "1") (pinfunction "1_1") (pintype "passive"))
    )
    (net (code "147") (name "/USER_TACT_SW1") (class "Default")
      (node (ref "R607") (pin "1") (pinfunction "1_1") (pintype "passive"))
    )
    (net (code "148") (name "/USER_TACT_SW2") (class "Default")
      (node (ref "R608") (pin "1") (pinfunction "1_1") (pintype "passive"))
    )
    (net (code "149") (name "/USER_TACT_SW3") (class "Default")
      (node (ref "R609") (pin "1") (pinfunction "1_1") (pintype "passive"))
    )
    (net (code "150") (name "/USER_TACT_SW4") (class "Default")
      (node (ref "R610") (pin "1") (pinfunction "1_1") (pintype "passive"))
    )
    (net (code "151") (name "DGND") (class "Default")
      (node (ref "CN600") (pin "103") (pinfunction "103_103") (pintype "passive"))
      (node (ref "CN600") (pin "104") (pinfunction "104_104") (pintype "passive"))
      (node (ref "CN600") (pin "109") (pinfunction "109_109") (pintype "passive"))
      (node (ref "CN600") (pin "110") (pinfunction "110_110") (pintype "passive"))
      (node (ref "CN600") (pin "115") (pinfunction "115_115") (pintype "passive"))
      (node (ref "CN600") (pin "116") (pinfunction "116_116") (pintype "passive"))
      (node (ref "CN600") (pin "121") (pinfunction "121_121") (pintype "passive"))
      (node (ref "CN600") (pin "122") (pinfunction "122_122") (pintype "passive"))
      (node (ref "CN600") (pin "123") (pinfunction "123_123") (pintype "passive"))
      (node (ref "CN600") (pin "124") (pinfunction "124_124") (pintype "passive"))
      (node (ref "CN600") (pin "125") (pinfunction "125_125") (pintype "passive"))
      (node (ref "CN600") (pin "126") (pinfunction "126_126") (pintype "passive"))
      (node (ref "CN600") (pin "127") (pinfunction "127_127") (pintype "passive"))
      (node (ref "CN600") (pin "128") (pinfunction "128_128") (pintype "passive"))
      (node (ref "CN600") (pin "129") (pinfunction "129_129") (pintype "passive"))
      (node (ref "CN600") (pin "13") (pinfunction "13_13") (pintype "passive"))
      (node (ref "CN600") (pin "130") (pinfunction "130_130") (pintype "passive"))
      (node (ref "CN600") (pin "14") (pinfunction "14_14") (pintype "passive"))
      (node (ref "CN600") (pin "15") (pinfunction "15_15") (pintype "passive"))
      (node (ref "CN600") (pin "157") (pinfunction "157_157") (pintype "passive"))
      (node (ref "CN600") (pin "158") (pinfunction "158_158") (pintype "passive"))
      (node (ref "CN600") (pin "159") (pinfunction "159_159") (pintype "passive"))
      (node (ref "CN600") (pin "16") (pinfunction "16_16") (pintype "passive"))
      (node (ref "CN600") (pin "160") (pinfunction "160_160") (pintype "passive"))
      (node (ref "CN600") (pin "161") (pinfunction "161_161") (pintype "passive"))
      (node (ref "CN600") (pin "162") (pinfunction "162_162") (pintype "passive"))
      (node (ref "CN600") (pin "163") (pinfunction "163_163") (pintype "passive"))
      (node (ref "CN600") (pin "164") (pinfunction "164_164") (pintype "passive"))
      (node (ref "CN600") (pin "165") (pinfunction "165_165") (pintype "passive"))
      (node (ref "CN600") (pin "166") (pinfunction "166_166") (pintype "passive"))
      (node (ref "CN600") (pin "17") (pinfunction "17_17") (pintype "passive"))
      (node (ref "CN600") (pin "171") (pinfunction "171_171") (pintype "passive"))
      (node (ref "CN600") (pin "172") (pinfunction "172_172") (pintype "passive"))
      (node (ref "CN600") (pin "177") (pinfunction "177_177") (pintype "passive"))
      (node (ref "CN600") (pin "178") (pinfunction "178_178") (pintype "passive"))
      (node (ref "CN600") (pin "18") (pinfunction "18_18") (pintype "passive"))
      (node (ref "CN600") (pin "183") (pinfunction "183_183") (pintype "passive"))
      (node (ref "CN600") (pin "184") (pinfunction "184_184") (pintype "passive"))
      (node (ref "CN600") (pin "189") (pinfunction "189_189") (pintype "passive"))
      (node (ref "CN600") (pin "19") (pinfunction "19_19") (pintype "passive"))
      (node (ref "CN600") (pin "190") (pinfunction "190_190") (pintype "passive"))
      (node (ref "CN600") (pin "195") (pinfunction "195_195") (pintype "passive"))
      (node (ref "CN600") (pin "196") (pinfunction "196_196") (pintype "passive"))
      (node (ref "CN600") (pin "20") (pinfunction "20_20") (pintype "passive"))
      (node (ref "CN600") (pin "201") (pinfunction "201_201") (pintype "passive"))
      (node (ref "CN600") (pin "202") (pinfunction "202_202") (pintype "passive"))
      (node (ref "CN600") (pin "207") (pinfunction "207_207") (pintype "passive"))
      (node (ref "CN600") (pin "208") (pinfunction "208_208") (pintype "passive"))
      (node (ref "CN600") (pin "21") (pinfunction "21_21") (pintype "passive"))
      (node (ref "CN600") (pin "213") (pinfunction "213_213") (pintype "passive"))
      (node (ref "CN600") (pin "214") (pinfunction "214_214") (pintype "passive"))
      (node (ref "CN600") (pin "219") (pinfunction "219_219") (pintype "passive"))
      (node (ref "CN600") (pin "22") (pinfunction "22_22") (pintype "passive"))
      (node (ref "CN600") (pin "220") (pinfunction "220_220") (pintype "passive"))
      (node (ref "CN600") (pin "225") (pinfunction "225_225") (pintype "passive"))
      (node (ref "CN600") (pin "226") (pinfunction "226_226") (pintype "passive"))
      (node (ref "CN600") (pin "231") (pinfunction "231_231") (pintype "passive"))
      (node (ref "CN600") (pin "232") (pinfunction "232_232") (pintype "passive"))
      (node (ref "CN600") (pin "237") (pinfunction "237_237") (pintype "passive"))
      (node (ref "CN600") (pin "238") (pinfunction "238_238") (pintype "passive"))
      (node (ref "CN600") (pin "253") (pinfunction "253_253") (pintype "passive"))
      (node (ref "CN600") (pin "254") (pinfunction "254_254") (pintype "passive"))
      (node (ref "CN600") (pin "255") (pinfunction "255_255") (pintype "passive"))
      (node (ref "CN600") (pin "256") (pinfunction "256_256") (pintype "passive"))
      (node (ref "CN600") (pin "257") (pinfunction "257_257") (pintype "passive"))
      (node (ref "CN600") (pin "258") (pinfunction "258_258") (pintype "passive"))
      (node (ref "CN600") (pin "259") (pinfunction "259_259") (pintype "passive"))
      (node (ref "CN600") (pin "260") (pinfunction "260_260") (pintype "passive"))
      (node (ref "CN600") (pin "37") (pinfunction "37_37") (pintype "passive"))
      (node (ref "CN600") (pin "38") (pinfunction "38_38") (pintype "passive"))
      (node (ref "CN600") (pin "43") (pinfunction "43_43") (pintype "passive"))
      (node (ref "CN600") (pin "44") (pinfunction "44_44") (pintype "passive"))
      (node (ref "CN600") (pin "49") (pinfunction "49_49") (pintype "passive"))
      (node (ref "CN600") (pin "50") (pinfunction "50_50") (pintype "passive"))
      (node (ref "CN600") (pin "55") (pinfunction "55_55") (pintype "passive"))
      (node (ref "CN600") (pin "56") (pinfunction "56_56") (pintype "passive"))
      (node (ref "CN600") (pin "61") (pinfunction "61_61") (pintype "passive"))
      (node (ref "CN600") (pin "62") (pinfunction "62_62") (pintype "passive"))
      (node (ref "CN600") (pin "67") (pinfunction "67_67") (pintype "passive"))
      (node (ref "CN600") (pin "68") (pinfunction "68_68") (pintype "passive"))
      (node (ref "CN600") (pin "73") (pinfunction "73_73") (pintype "passive"))
      (node (ref "CN600") (pin "74") (pinfunction "74_74") (pintype "passive"))
      (node (ref "CN600") (pin "79") (pinfunction "79_79") (pintype "passive"))
      (node (ref "CN600") (pin "80") (pinfunction "80_80") (pintype "passive"))
      (node (ref "CN600") (pin "85") (pinfunction "85_85") (pintype "passive"))
      (node (ref "CN600") (pin "86") (pinfunction "86_86") (pintype "passive"))
      (node (ref "CN600") (pin "91") (pinfunction "91_91") (pintype "passive"))
      (node (ref "CN600") (pin "92") (pinfunction "92_92") (pintype "passive"))
      (node (ref "CN600") (pin "97") (pinfunction "97_97") (pintype "passive"))
      (node (ref "CN600") (pin "98") (pinfunction "98_98") (pintype "passive"))
      (node (ref "CN601") (pin "68") (pinfunction "68_68") (pintype "passive"))
      (node (ref "CN601") (pin "70") (pinfunction "70_70") (pintype "passive"))
      (node (ref "CN601") (pin "72") (pinfunction "72_72") (pintype "passive"))
      (node (ref "CN601") (pin "74") (pinfunction "74_74") (pintype "passive"))
    )
    (net (code "152") (name "DP1.0VS_FPGA") (class "Default")
      (node (ref "CN600") (pin "133") (pinfunction "133_133") (pintype "passive"))
      (node (ref "CN600") (pin "134") (pinfunction "134_134") (pintype "passive"))
      (node (ref "CN600") (pin "135") (pinfunction "135_135") (pintype "passive"))
      (node (ref "CN600") (pin "136") (pinfunction "136_136") (pintype "passive"))
      (node (ref "CN600") (pin "137") (pinfunction "137_137") (pintype "passive"))
      (node (ref "CN600") (pin "138") (pinfunction "138_138") (pintype "passive"))
      (node (ref "CN600") (pin "139") (pinfunction "139_139") (pintype "passive"))
      (node (ref "CN600") (pin "140") (pinfunction "140_140") (pintype "passive"))
      (node (ref "CN600") (pin "141") (pinfunction "141_141") (pintype "passive"))
      (node (ref "CN600") (pin "142") (pinfunction "142_142") (pintype "passive"))
    )
    (net (code "153") (name "DP1.8VS_FPGA") (class "Default")
      (node (ref "CN600") (pin "145") (pinfunction "145_145") (pintype "passive"))
      (node (ref "CN600") (pin "146") (pinfunction "146_146") (pintype "passive"))
      (node (ref "CN600") (pin "147") (pinfunction "147_147") (pintype "passive"))
      (node (ref "CN600") (pin "148") (pinfunction "148_148") (pintype "passive"))
      (node (ref "CN600") (pin "149") (pinfunction "149_149") (pintype "passive"))
      (node (ref "CN600") (pin "150") (pinfunction "150_150") (pintype "passive"))
      (node (ref "CN600") (pin "151") (pinfunction "151_151") (pintype "passive"))
      (node (ref "CN600") (pin "152") (pinfunction "152_152") (pintype "passive"))
      (node (ref "CN600") (pin "153") (pinfunction "153_153") (pintype "passive"))
      (node (ref "CN600") (pin "154") (pinfunction "154_154") (pintype "passive"))
    )
    (net (code "154") (name "DP1.35VS_FPGA") (class "Default")
      (node (ref "CN600") (pin "25") (pinfunction "25_25") (pintype "passive"))
      (node (ref "CN600") (pin "26") (pinfunction "26_26") (pintype "passive"))
      (node (ref "CN600") (pin "27") (pinfunction "27_27") (pintype "passive"))
      (node (ref "CN600") (pin "28") (pinfunction "28_28") (pintype "passive"))
      (node (ref "CN600") (pin "29") (pinfunction "29_29") (pintype "passive"))
      (node (ref "CN600") (pin "30") (pinfunction "30_30") (pintype "passive"))
      (node (ref "CN600") (pin "31") (pinfunction "31_31") (pintype "passive"))
      (node (ref "CN600") (pin "32") (pinfunction "32_32") (pintype "passive"))
      (node (ref "CN600") (pin "33") (pinfunction "33_33") (pintype "passive"))
      (node (ref "CN600") (pin "34") (pinfunction "34_34") (pintype "passive"))
    )
    (net (code "155") (name "DP3.3VS") (class "Default")
      (node (ref "R645") (pin "1") (pinfunction "1_1") (pintype "passive"))
    )
    (net (code "156") (name "DP3.3VS_FPGA") (class "Default")
      (node (ref "CN600") (pin "241") (pinfunction "241_241") (pintype "passive"))
      (node (ref "CN600") (pin "242") (pinfunction "242_242") (pintype "passive"))
      (node (ref "CN600") (pin "243") (pinfunction "243_243") (pintype "passive"))
      (node (ref "CN600") (pin "244") (pinfunction "244_244") (pintype "passive"))
      (node (ref "CN600") (pin "245") (pinfunction "245_245") (pintype "passive"))
      (node (ref "CN600") (pin "246") (pinfunction "246_246") (pintype "passive"))
      (node (ref "CN600") (pin "247") (pinfunction "247_247") (pintype "passive"))
      (node (ref "CN600") (pin "248") (pinfunction "248_248") (pintype "passive"))
      (node (ref "CN600") (pin "249") (pinfunction "249_249") (pintype "passive"))
      (node (ref "CN600") (pin "250") (pinfunction "250_250") (pintype "passive"))
    )
    (net (code "157") (name "DP5VS") (class "Default")
      (node (ref "CN600") (pin "1") (pinfunction "1_1") (pintype "passive"))
      (node (ref "CN600") (pin "10") (pinfunction "10_10") (pintype "passive"))
      (node (ref "CN600") (pin "2") (pinfunction "2_2") (pintype "passive"))
      (node (ref "CN600") (pin "3") (pinfunction "3_3") (pintype "passive"))
      (node (ref "CN600") (pin "4") (pinfunction "4_4") (pintype "passive"))
      (node (ref "CN600") (pin "5") (pinfunction "5_5") (pintype "passive"))
      (node (ref "CN600") (pin "6") (pinfunction "6_6") (pintype "passive"))
      (node (ref "CN600") (pin "7") (pinfunction "7_7") (pintype "passive"))
      (node (ref "CN600") (pin "8") (pinfunction "8_8") (pintype "passive"))
      (node (ref "CN600") (pin "9") (pinfunction "9_9") (pintype "passive"))
      (node (ref "R620") (pin "2") (pinfunction "2_2") (pintype "passive"))
    )
    (net (code "158") (name "unconnected-(CN600-Pad11)") (class "Default")
      (node (ref "CN600") (pin "11") (pinfunction "11_11") (pintype "passive+no_connect"))
    )
    (net (code "159") (name "unconnected-(CN600-Pad12)") (class "Default")
      (node (ref "CN600") (pin "12") (pinfunction "12_12") (pintype "passive+no_connect"))
    )
    (net (code "160") (name "unconnected-(CN600-Pad23)") (class "Default")
      (node (ref "CN600") (pin "23") (pinfunction "23_23") (pintype "passive+no_connect"))
    )
    (net (code "161") (name "unconnected-(CN600-Pad24)") (class "Default")
      (node (ref "CN600") (pin "24") (pinfunction "24_24") (pintype "passive+no_connect"))
    )
    (net (code "162") (name "unconnected-(CN600-Pad35)") (class "Default")
      (node (ref "CN600") (pin "35") (pinfunction "35_35") (pintype "passive+no_connect"))
    )
    (net (code "163") (name "unconnected-(CN600-Pad36)") (class "Default")
      (node (ref "CN600") (pin "36") (pinfunction "36_36") (pintype "passive+no_connect"))
    )
    (net (code "164") (name "unconnected-(CN600-Pad131)") (class "Default")
      (node (ref "CN600") (pin "131") (pinfunction "131_131") (pintype "passive+no_connect"))
    )
    (net (code "165") (name "unconnected-(CN600-Pad132)") (class "Default")
      (node (ref "CN600") (pin "132") (pinfunction "132_132") (pintype "passive+no_connect"))
    )
    (net (code "166") (name "unconnected-(CN600-Pad143)") (class "Default")
      (node (ref "CN600") (pin "143") (pinfunction "143_143") (pintype "passive+no_connect"))
    )
    (net (code "167") (name "unconnected-(CN600-Pad144)") (class "Default")
      (node (ref "CN600") (pin "144") (pinfunction "144_144") (pintype "passive+no_connect"))
    )
    (net (code "168") (name "unconnected-(CN600-Pad155)") (class "Default")
      (node (ref "CN600") (pin "155") (pinfunction "155_155") (pintype "passive+no_connect"))
    )
    (net (code "169") (name "unconnected-(CN600-Pad156)") (class "Default")
      (node (ref "CN600") (pin "156") (pinfunction "156_156") (pintype "passive+no_connect"))
    )
    (net (code "170") (name "unconnected-(CN600-Pad239)") (class "Default")
      (node (ref "CN600") (pin "239") (pinfunction "239_239") (pintype "passive+no_connect"))
    )
    (net (code "171") (name "unconnected-(CN600-Pad240)") (class "Default")
      (node (ref "CN600") (pin "240") (pinfunction "240_240") (pintype "passive+no_connect"))
    )
    (net (code "172") (name "unconnected-(CN600-Pad251)") (class "Default")
      (node (ref "CN600") (pin "251") (pinfunction "251_251") (pintype "passive+no_connect"))
    )
    (net (code "173") (name "unconnected-(CN600-Pad252)") (class "Default")
      (node (ref "CN600") (pin "252") (pinfunction "252_252") (pintype "passive+no_connect"))
    )
    (net (code "174") (name "unconnected-(CN600-PadMP)") (class "Default")
      (node (ref "CN600") (pin "MP") (pinfunction "MP_MP") (pintype "passive"))
    )
    (net (code "175") (name "unconnected-(CN601-Pad3)") (class "Default")
      (node (ref "CN601") (pin "3") (pinfunction "3_3") (pintype "passive+no_connect"))
    )
    (net (code "176") (name "unconnected-(CN601-Pad4)") (class "Default")
      (node (ref "CN601") (pin "4") (pinfunction "4_4") (pintype "passive+no_connect"))
    )
    (net (code "177") (name "unconnected-(CN601-Pad7)") (class "Default")
      (node (ref "CN601") (pin "7") (pinfunction "7_7") (pintype "passive+no_connect"))
    )
    (net (code "178") (name "unconnected-(CN601-Pad8)") (class "Default")
      (node (ref "CN601") (pin "8") (pinfunction "8_8") (pintype "passive+no_connect"))
    )
    (net (code "179") (name "unconnected-(CN601-Pad11)") (class "Default")
      (node (ref "CN601") (pin "11") (pinfunction "11_11") (pintype "passive+no_connect"))
    )
    (net (code "180") (name "unconnected-(CN601-Pad12)") (class "Default")
      (node (ref "CN601") (pin "12") (pinfunction "12_12") (pintype "passive+no_connect"))
    )
    (net (code "181") (name "unconnected-(CN601-Pad14)") (class "Default")
      (node (ref "CN601") (pin "14") (pinfunction "14_14") (pintype "passive+no_connect"))
    )
    (net (code "182") (name "unconnected-(CN601-Pad15)") (class "Default")
      (node (ref "CN601") (pin "15") (pinfunction "15_15") (pintype "passive+no_connect"))
    )
    (net (code "183") (name "unconnected-(CN601-Pad16)") (class "Default")
      (node (ref "CN601") (pin "16") (pinfunction "16_16") (pintype "passive+no_connect"))
    )
    (net (code "184") (name "unconnected-(CN601-Pad18)") (class "Default")
      (node (ref "CN601") (pin "18") (pinfunction "18_18") (pintype "passive+no_connect"))
    )
    (net (code "185") (name "unconnected-(CN601-Pad19)") (class "Default")
      (node (ref "CN601") (pin "19") (pinfunction "19_19") (pintype "passive+no_connect"))
    )
    (net (code "186") (name "unconnected-(CN601-Pad20)") (class "Default")
      (node (ref "CN601") (pin "20") (pinfunction "20_20") (pintype "passive+no_connect"))
    )
    (net (code "187") (name "unconnected-(CN601-Pad21)") (class "Default")
      (node (ref "CN601") (pin "21") (pinfunction "21_21") (pintype "passive+no_connect"))
    )
    (net (code "188") (name "unconnected-(CN601-Pad22)") (class "Default")
      (node (ref "CN601") (pin "22") (pinfunction "22_22") (pintype "passive+no_connect"))
    )
    (net (code "189") (name "unconnected-(CN601-Pad23)") (class "Default")
      (node (ref "CN601") (pin "23") (pinfunction "23_23") (pintype "passive+no_connect"))
    )
    (net (code "190") (name "unconnected-(CN601-Pad24)") (class "Default")
      (node (ref "CN601") (pin "24") (pinfunction "24_24") (pintype "passive+no_connect"))
    )
    (net (code "191") (name "unconnected-(CN601-Pad25)") (class "Default")
      (node (ref "CN601") (pin "25") (pinfunction "25_25") (pintype "passive+no_connect"))
    )
    (net (code "192") (name "unconnected-(CN601-Pad26)") (class "Default")
      (node (ref "CN601") (pin "26") (pinfunction "26_26") (pintype "passive+no_connect"))
    )
    (net (code "193") (name "unconnected-(CN601-Pad27)") (class "Default")
      (node (ref "CN601") (pin "27") (pinfunction "27_27") (pintype "passive+no_connect"))
    )
    (net (code "194") (name "unconnected-(CN601-Pad28)") (class "Default")
      (node (ref "CN601") (pin "28") (pinfunction "28_28") (pintype "passive+no_connect"))
    )
    (net (code "195") (name "unconnected-(CN601-Pad29)") (class "Default")
      (node (ref "CN601") (pin "29") (pinfunction "29_29") (pintype "passive+no_connect"))
    )
    (net (code "196") (name "unconnected-(CN601-Pad30)") (class "Default")
      (node (ref "CN601") (pin "30") (pinfunction "30_30") (pintype "passive+no_connect"))
    )
    (net (code "197") (name "unconnected-(CN601-Pad31)") (class "Default")
      (node (ref "CN601") (pin "31") (pinfunction "31_31") (pintype "passive+no_connect"))
    )
    (net (code "198") (name "unconnected-(CN601-Pad32)") (class "Default")
      (node (ref "CN601") (pin "32") (pinfunction "32_32") (pintype "passive+no_connect"))
    )
    (net (code "199") (name "unconnected-(CN601-Pad33)") (class "Default")
      (node (ref "CN601") (pin "33") (pinfunction "33_33") (pintype "passive+no_connect"))
    )
    (net (code "200") (name "unconnected-(CN601-Pad34)") (class "Default")
      (node (ref "CN601") (pin "34") (pinfunction "34_34") (pintype "passive+no_connect"))
    )
    (net (code "201") (name "unconnected-(CN601-Pad35)") (class "Default")
      (node (ref "CN601") (pin "35") (pinfunction "35_35") (pintype "passive+no_connect"))
    )
    (net (code "202") (name "unconnected-(CN601-Pad36)") (class "Default")
      (node (ref "CN601") (pin "36") (pinfunction "36_36") (pintype "passive+no_connect"))
    )
    (net (code "203") (name "unconnected-(CN601-Pad37)") (class "Default")
      (node (ref "CN601") (pin "37") (pinfunction "37_37") (pintype "passive+no_connect"))
    )
    (net (code "204") (name "unconnected-(CN601-Pad38)") (class "Default")
      (node (ref "CN601") (pin "38") (pinfunction "38_38") (pintype "passive+no_connect"))
    )
    (net (code "205") (name "unconnected-(CN601-Pad39)") (class "Default")
      (node (ref "CN601") (pin "39") (pinfunction "39_39") (pintype "passive+no_connect"))
    )
    (net (code "206") (name "unconnected-(CN601-Pad40)") (class "Default")
      (node (ref "CN601") (pin "40") (pinfunction "40_40") (pintype "passive+no_connect"))
    )
    (net (code "207") (name "unconnected-(CN601-Pad41)") (class "Default")
      (node (ref "CN601") (pin "41") (pinfunction "41_41") (pintype "passive+no_connect"))
    )
    (net (code "208") (name "unconnected-(CN601-Pad42)") (class "Default")
      (node (ref "CN601") (pin "42") (pinfunction "42_42") (pintype "passive+no_connect"))
    )
    (net (code "209") (name "unconnected-(CN601-Pad43)") (class "Default")
      (node (ref "CN601") (pin "43") (pinfunction "43_43") (pintype "passive+no_connect"))
    )
    (net (code "210") (name "unconnected-(CN601-Pad44)") (class "Default")
      (node (ref "CN601") (pin "44") (pinfunction "44_44") (pintype "passive+no_connect"))
    )
    (net (code "211") (name "unconnected-(CN601-Pad45)") (class "Default")
      (node (ref "CN601") (pin "45") (pinfunction "45_45") (pintype "passive+no_connect"))
    )
    (net (code "212") (name "unconnected-(CN601-Pad46)") (class "Default")
      (node (ref "CN601") (pin "46") (pinfunction "46_46") (pintype "passive+no_connect"))
    )
    (net (code "213") (name "unconnected-(CN601-Pad47)") (class "Default")
      (node (ref "CN601") (pin "47") (pinfunction "47_47") (pintype "passive+no_connect"))
    )
    (net (code "214") (name "unconnected-(CN601-Pad48)") (class "Default")
      (node (ref "CN601") (pin "48") (pinfunction "48_48") (pintype "passive+no_connect"))
    )
    (net (code "215") (name "unconnected-(CN601-Pad49)") (class "Default")
      (node (ref "CN601") (pin "49") (pinfunction "49_49") (pintype "passive+no_connect"))
    )
    (net (code "216") (name "unconnected-(CN601-Pad50)") (class "Default")
      (node (ref "CN601") (pin "50") (pinfunction "50_50") (pintype "passive+no_connect"))
    )
    (net (code "217") (name "unconnected-(CN601-Pad51)") (class "Default")
      (node (ref "CN601") (pin "51") (pinfunction "51_51") (pintype "passive+no_connect"))
    )
    (net (code "218") (name "unconnected-(CN601-Pad52)") (class "Default")
      (node (ref "CN601") (pin "52") (pinfunction "52_52") (pintype "passive+no_connect"))
    )
    (net (code "219") (name "unconnected-(CN601-Pad53)") (class "Default")
      (node (ref "CN601") (pin "53") (pinfunction "53_53") (pintype "passive+no_connect"))
    )
    (net (code "220") (name "unconnected-(CN601-Pad54)") (class "Default")
      (node (ref "CN601") (pin "54") (pinfunction "54_54") (pintype "passive+no_connect"))
    )
    (net (code "221") (name "unconnected-(CN601-Pad55)") (class "Default")
      (node (ref "CN601") (pin "55") (pinfunction "55_55") (pintype "passive+no_connect"))
    )
    (net (code "222") (name "unconnected-(CN601-Pad56)") (class "Default")
      (node (ref "CN601") (pin "56") (pinfunction "56_56") (pintype "passive+no_connect"))
    )
    (net (code "223") (name "unconnected-(CN601-Pad57)") (class "Default")
      (node (ref "CN601") (pin "57") (pinfunction "57_57") (pintype "passive+no_connect"))
    )
    (net (code "224") (name "unconnected-(CN601-Pad58)") (class "Default")
      (node (ref "CN601") (pin "58") (pinfunction "58_58") (pintype "passive+no_connect"))
    )
    (net (code "225") (name "unconnected-(CN601-SHIELD-PadS1)") (class "Default")
      (node (ref "CN601") (pin "S1") (pinfunction "SHIELD_S1") (pintype "passive+no_connect"))
    )
    (net (code "226") (name "unconnected-(CN601-SHIELD-PadS2)") (class "Default")
      (node (ref "CN601") (pin "S2") (pinfunction "SHIELD_S2") (pintype "passive+no_connect"))
    )
    (net (code "227") (name "unconnected-(H600-Pad1)") (class "Default")
      (node (ref "H600") (pin "1") (pinfunction "1_1") (pintype "passive+no_connect"))
    )
  )
)
